# 05_Supply_Power.net
KiCad netlist of a schematic drawn in Altium Designer
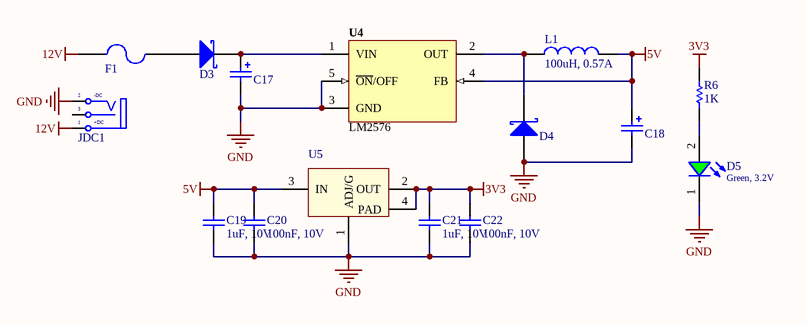
[diagram p0: 05_Supply_Power.SchDoc]

(export (version "E")
  (design (tool "Eeschema 10.0.6"))
  (components
    (comp (ref "C17")
      (value "100uF")
      (footprint "WCAP-ATG8_D6.3H11")
      (description "WCAP-ATG8 Aluminum Electrolytic Capacitor, Radial THT, D6.3xH11mm, 100uF, 25V")
      (fields
        (field (name "MANUFACTURER") "Wurth Elektronik")
        (field (name "MANUFACTURER PART NUMBER") "860010473007")
      )
      (libsource (lib "Altium_WCAP-ATG8 (rev22a)") (part "860010473007"))
    )
    (comp (ref "C18")
      (value "1000uF")
      (footprint "WCAP-ATG8_D10H20")
      (description "WCAP-ATG8 Aluminum Electrolytic Capacitor, Radial THT, D10xH20mm, 1000uF, 25V")
      (fields
        (field (name "MANUFACTURER") "Wurth Elektronik")
        (field (name "MANUFACTURER PART NUMBER") "860010475017")
      )
      (libsource (lib "Altium_WCAP-ATG8 (rev22a)") (part "860010475017"))
    )
    (comp (ref "C19")
      (value "1uF, 10V")
      (footprint "WCAP-CSGP_0603_H=0.8mm_Reflow")
      (description "WCAP-CSGP Multilayer Ceramic Chip Capacitor, General Purpose, size 0603, X5R, 1uF, 10V")
      (fields
        (field (name "MANUFACTURER PART NUMBER") "885012106010")
        (field (name "MANUFACTURER") "Wurth Elektronik")
      )
      (libsource (lib "Altium_WCAP-CSGP (rev20a)") (part "885012106010"))
    )
    (comp (ref "C20")
      (value "100nF, 10V")
      (footprint "WCAP-CSGP_0603_H=0.8mm_Reflow")
      (description "WCAP-CSGP Multilayer Ceramic Chip Capacitor, General Purpose, size 0603, X7R, 100nF, 10V")
      (fields
        (field (name "MANUFACTURER PART NUMBER") "885012206020")
        (field (name "MANUFACTURER") "Wurth Elektronik")
      )
      (libsource (lib "Altium_WCAP-CSGP (rev20a)") (part "885012206020"))
    )
    (comp (ref "C21")
      (value "1uF, 10V")
      (footprint "WCAP-CSGP_0603_H=0.8mm_Reflow")
      (description "WCAP-CSGP Multilayer Ceramic Chip Capacitor, General Purpose, size 0603, X5R, 1uF, 10V")
      (fields
        (field (name "MANUFACTURER PART NUMBER") "885012106010")
        (field (name "MANUFACTURER") "Wurth Elektronik")
      )
      (libsource (lib "Altium_WCAP-CSGP (rev20a)") (part "885012106010"))
    )
    (comp (ref "C22")
      (value "100nF, 10V")
      (footprint "WCAP-CSGP_0603_H=0.8mm_Reflow")
      (description "WCAP-CSGP Multilayer Ceramic Chip Capacitor, General Purpose, size 0603, X7R, 100nF, 10V")
      (fields
        (field (name "MANUFACTURER PART NUMBER") "885012206020")
        (field (name "MANUFACTURER") "Wurth Elektronik")
      )
      (libsource (lib "Altium_WCAP-CSGP (rev20a)") (part "885012206020"))
    )
    (comp (ref "D3")
      (value "D Schottky")
      (footprint "SS34")
      (description "Schottky Diode")
      (fields (field (name "PUBLISHER") "Altium Limited"))
      (libsource (lib "PIF_Library") (part "D Schottky"))
    )
    (comp (ref "D4")
      (value "D Schottky")
      (footprint "SS34")
      (description "Schottky Diode")
      (fields (field (name "PUBLISHER") "Altium Limited"))
      (libsource (lib "PIF_Library") (part "D Schottky"))
    )
    (comp (ref "D5")
      (value "Green, 3.2V")
      (footprint "WL-SMCW_0603_H=0.25mm")
      (description "WL-SMCW SMT Mono-color Chip LED Waterclear, size 0603, Green, 3.2V, 140deg")
      (fields (field (name "PART NUMBER") "150060GS75020") (field (name "PUBLISHER") "Wurth Elektronik"))
      (libsource (lib "Altium_WL-SMCW (rev20a)") (part "150060GS75020"))
    )
    (comp (ref "F1") (value "Fuse") (footprint "FUSE SMD") (libsource (lib "PIF_Library") (part "Fuse")))
    (comp (ref "JDC1")
      (value "Jack DC")
      (footprint "DC-IN")
      (description "Jack DC input")
      (libsource (lib "PIF_Library") (part "Jack DC"))
    )
    (comp (ref "L1")
      (value "100uH, 0.57A")
      (footprint "WE-PD2A_5848")
      (description "WE-PD2A SMT Power Inductor, size 5848, 100uH, 0.57A")
      (fields
        (field (name "MANUFACTURER PART NUMBER") "78477420")
        (field (name "MANUFACTURER") "Wurth Elektronik")
      )
      (libsource (lib "Altium_WE-PD2A (rev20a)") (part "78477420"))
    )
    (comp (ref "R6")
      (value "1K")
      (footprint "RES-SM-0603")
      (description "Resistor")
      (fields (field (name "Comment") "RESISTOR SMD"))
      (libsource (lib "PIF_Library") (part "RESISTOR SMD"))
    )
    (comp (ref "U4")
      (value "LM2576")
      (footprint "TO263")
      (libsource (lib "TechMT.VN_Lib_Project v2") (part "LM2576"))
    )
    (comp (ref "U5")
      (value "LM1117")
      (footprint "SOT223-4N")
      (description "Available in 1.8V, 2.5V, 2.85V, 3.3V, 5V, and  Adjustable Versions")
      (libsource (lib "PIF_Library") (part "LM1117"))
    )
  )
  (nets
    (net (code "1") (name "3V3") (class "Default")
      (node (ref "C21") (pin "2") (pinfunction "2_2") (pintype "passive"))
      (node (ref "C22") (pin "2") (pinfunction "2_2") (pintype "passive"))
      (node (ref "R6") (pin "2") (pinfunction "2_2") (pintype "passive"))
      (node (ref "U5") (pin "2") (pinfunction "OUT_2") (pintype "passive"))
      (node (ref "U5") (pin "4") (pinfunction "PAD_4") (pintype "passive"))
    )
    (net (code "2") (name "5V") (class "Default")
      (node (ref "C18") (pin "1") (pinfunction "P_1") (pintype "passive"))
      (node (ref "C19") (pin "2") (pinfunction "2_2") (pintype "passive"))
      (node (ref "C20") (pin "2") (pinfunction "2_2") (pintype "passive"))
      (node (ref "L1") (pin "2") (pinfunction "2_2") (pintype "passive"))
      (node (ref "U4") (pin "4") (pinfunction "FB_4") (pintype "input"))
      (node (ref "U5") (pin "3") (pinfunction "IN_3") (pintype "passive"))
    )
    (net (code "3") (name "12V") (class "Default")
      (node (ref "F1") (pin "1") (pinfunction "1_1") (pintype "passive"))
      (node (ref "JDC1") (pin "1") (pinfunction "T_1") (pintype "passive"))
    )
    (net (code "4") (name "GND") (class "Default")
      (node (ref "C17") (pin "2") (pinfunction "N_2") (pintype "passive"))
      (node (ref "C18") (pin "2") (pinfunction "N_2") (pintype "passive"))
      (node (ref "C19") (pin "1") (pinfunction "1_1") (pintype "passive"))
      (node (ref "C20") (pin "1") (pinfunction "1_1") (pintype "passive"))
      (node (ref "C21") (pin "1") (pinfunction "1_1") (pintype "passive"))
      (node (ref "C22") (pin "1") (pinfunction "1_1") (pintype "passive"))
      (node (ref "D4") (pin "1") (pinfunction "A_1") (pintype "passive"))
      (node (ref "D5") (pin "1") (pinfunction "K_1") (pintype "passive"))
      (node (ref "JDC1") (pin "2") (pinfunction "TN_2") (pintype "passive"))
      (node (ref "U4") (pin "3") (pinfunction "GND_3") (pintype "power_in"))
      (node (ref "U4") (pin "5") (pinfunction "~{ON}/OFF_5") (pintype "input"))
      (node (ref "U5") (pin "1") (pinfunction "ADJ/G_1") (pintype "passive"))
    )
    (net (code "5") (name "Net-(C17-P)") (class "Default")
      (node (ref "C17") (pin "1") (pinfunction "P_1") (pintype "passive"))
      (node (ref "D3") (pin "2") (pinfunction "K_2") (pintype "passive"))
      (node (ref "U4") (pin "1") (pinfunction "VIN_1") (pintype "power_in"))
    )
    (net (code "6") (name "Net-(D3-A)") (class "Default")
      (node (ref "D3") (pin "1") (pinfunction "A_1") (pintype "passive"))
      (node (ref "F1") (pin "2") (pinfunction "2_2") (pintype "passive"))
    )
    (net (code "7") (name "Net-(D4-K)") (class "Default")
      (node (ref "D4") (pin "2") (pinfunction "K_2") (pintype "passive"))
      (node (ref "L1") (pin "1") (pinfunction "1_1") (pintype "passive"))
      (node (ref "U4") (pin "2") (pinfunction "OUT_2") (pintype "power_in"))
    )
    (net (code "8") (name "Net-(D5-A)") (class "Default")
      (node (ref "D5") (pin "2") (pinfunction "A_2") (pintype "passive"))
      (node (ref "R6") (pin "1") (pinfunction "1_1") (pintype "passive"))
    )
    (net (code "9") (name "unconnected-(JDC1-S-Pad3)") (class "Default")
      (node (ref "JDC1") (pin "3") (pinfunction "S_3") (pintype "power_in"))
    )
  )
)
